# CAMERA_DVP_FPC24_OV2640_8bit.net
KiCad netlist of a schematic drawn in Altium Designer
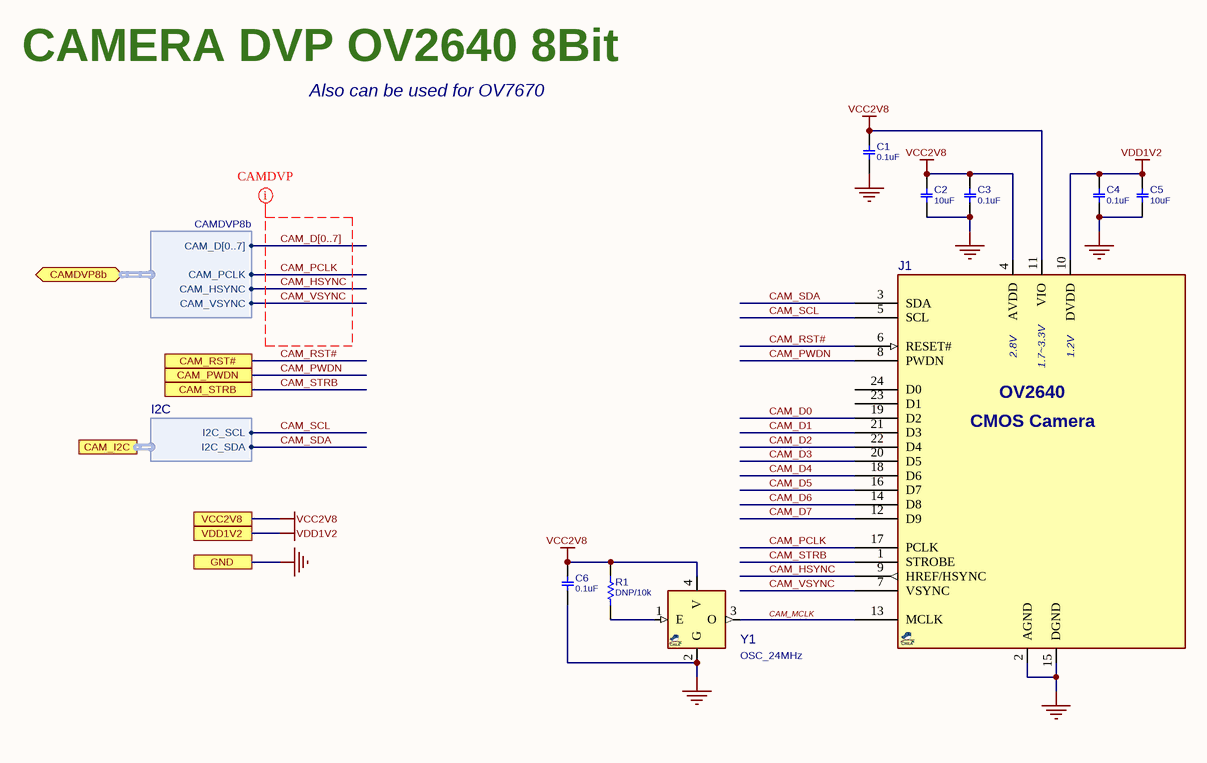
[diagram p0: CAMERA_DVP_FPC24_OV2640_8bit.SchDoc]

(export (version "E")
  (design (tool "Eeschema 10.0.6"))
  (components
    (comp (ref "C1")
      (value "0.1uF")
      (footprint "C0402")
      (description "CAP, MLCC")
      (libsource (lib "mlcc_smd_passive") (part "CAP_SMD_MLCC_100n50TDK"))
    )
    (comp (ref "C2")
      (value "10uF")
      (footprint "C0402")
      (description "CAP, MLCC")
      (libsource (lib "mlcc_smd_passive") (part "CAP_SMD_MLCC_100n50TDK"))
    )
    (comp (ref "C3")
      (value "0.1uF")
      (footprint "C0402")
      (description "CAP, MLCC")
      (libsource (lib "mlcc_smd_passive") (part "CAP_SMD_MLCC_100n50TDK"))
    )
    (comp (ref "C4")
      (value "0.1uF")
      (footprint "C0402")
      (description "CAP, MLCC")
      (libsource (lib "mlcc_smd_passive") (part "CAP_SMD_MLCC_100n50TDK"))
    )
    (comp (ref "C5")
      (value "10uF")
      (footprint "C0402")
      (description "CAP, MLCC")
      (libsource (lib "mlcc_smd_passive") (part "CAP_SMD_MLCC_100n50TDK"))
    )
    (comp (ref "C6")
      (value "0.1uF")
      (footprint "C0402")
      (description "CAP, MLCC")
      (libsource (lib "mlcc_smd_passive") (part "CAP_SMD_MLCC_100n50TDK"))
    )
    (comp (ref "J1")
      (value "OV2640")
      (footprint "FPC50_24")
      (description "Camera Module, Color CMOS 2MP, DVP FPC24")
      (libsource (lib "camera") (part "OV2640_FPC24"))
    )
    (comp (ref "R1")
      (value "DNP/10k")
      (footprint "R0402")
      (description "RESISTOR, SMD, THICK FILM, YAGEO")
      (fields (field (name "MANF_P#") "RC0402FR-071KL") (field (name "MANF") "Yageo"))
      (libsource (lib "res_smd_Yageo0402_thickfilm") (part "RES_SMD_1K_0402YK"))
    )
    (comp (ref "Y1")
      (value "OSC_24MHz")
      (footprint "XTL_4_2016")
      (description "CLOCK OSCILLATOR")
      (fields (field (name "MANF") "ECS"))
      (libsource (lib "crystal_osc") (part "OSC_4_25MHz_3225E"))
    )
  )
  (nets
    (net (code "3") (name "/CAM_D0") (class "Default")
      (node (ref "J1") (pin "19") (pinfunction "D2_19") (pintype "passive"))
    )
    (net (code "4") (name "/CAM_D1") (class "Default")
      (node (ref "J1") (pin "21") (pinfunction "D3_21") (pintype "passive"))
    )
    (net (code "5") (name "/CAM_D2") (class "Default")
      (node (ref "J1") (pin "22") (pinfunction "D4_22") (pintype "passive"))
    )
    (net (code "6") (name "/CAM_D3") (class "Default")
      (node (ref "J1") (pin "20") (pinfunction "D5_20") (pintype "passive"))
    )
    (net (code "7") (name "/CAM_D4") (class "Default")
      (node (ref "J1") (pin "18") (pinfunction "D6_18") (pintype "passive"))
    )
    (net (code "8") (name "/CAM_D5") (class "Default")
      (node (ref "J1") (pin "16") (pinfunction "D7_16") (pintype "passive"))
    )
    (net (code "9") (name "/CAM_D6") (class "Default")
      (node (ref "J1") (pin "14") (pinfunction "D8_14") (pintype "passive"))
    )
    (net (code "10") (name "/CAM_D7") (class "Default")
      (node (ref "J1") (pin "12") (pinfunction "D9_12") (pintype "passive"))
    )
    (net (code "12") (name "/CAM_HSYNC") (class "Default")
      (node (ref "J1") (pin "9") (pinfunction "HREF/HSYNC_9") (pintype "output"))
    )
    (net (code "13") (name "/CAM_MCLK") (class "Default")
      (node (ref "J1") (pin "13") (pinfunction "MCLK_13") (pintype "passive"))
      (node (ref "Y1") (pin "3") (pinfunction "O_3") (pintype "output"))
    )
    (net (code "14") (name "/CAM_PCLK") (class "Default")
      (node (ref "J1") (pin "17") (pinfunction "PCLK_17") (pintype "passive"))
    )
    (net (code "15") (name "/CAM_PWDN") (class "Default")
      (node (ref "J1") (pin "8") (pinfunction "PWDN_8") (pintype "passive"))
    )
    (net (code "16") (name "/CAM_RST#") (class "Default")
      (node (ref "J1") (pin "6") (pinfunction "RESET#_6") (pintype "input"))
    )
    (net (code "17") (name "/CAM_SCL") (class "Default")
      (node (ref "J1") (pin "5") (pinfunction "SCL_5") (pintype "passive"))
    )
    (net (code "18") (name "/CAM_SDA") (class "Default")
      (node (ref "J1") (pin "3") (pinfunction "SDA_3") (pintype "passive"))
    )
    (net (code "19") (name "/CAM_STRB") (class "Default")
      (node (ref "J1") (pin "1") (pinfunction "STROBE_1") (pintype "passive"))
    )
    (net (code "20") (name "/CAM_VSYNC") (class "Default")
      (node (ref "J1") (pin "7") (pinfunction "VSYNC_7") (pintype "passive"))
    )
    (net (code "23") (name "GND") (class "Default")
      (node (ref "C1") (pin "2") (pinfunction "2_2") (pintype "passive"))
      (node (ref "C2") (pin "2") (pinfunction "2_2") (pintype "passive"))
      (node (ref "C3") (pin "2") (pinfunction "2_2") (pintype "passive"))
      (node (ref "C4") (pin "2") (pinfunction "2_2") (pintype "passive"))
      (node (ref "C5") (pin "2") (pinfunction "2_2") (pintype "passive"))
      (node (ref "C6") (pin "2") (pinfunction "2_2") (pintype "passive"))
      (node (ref "J1") (pin "15") (pinfunction "DGND_15") (pintype "power_in"))
      (node (ref "J1") (pin "2") (pinfunction "AGND_2") (pintype "power_in"))
      (node (ref "Y1") (pin "2") (pinfunction "G_2") (pintype "power_in"))
    )
    (net (code "24") (name "Net-(Y1-E)") (class "Default")
      (node (ref "R1") (pin "2") (pinfunction "2_2") (pintype "passive"))
      (node (ref "Y1") (pin "1") (pinfunction "E_1") (pintype "input"))
    )
    (net (code "25") (name "VCC2V8") (class "Default")
      (node (ref "C1") (pin "1") (pinfunction "1_1") (pintype "passive"))
      (node (ref "C2") (pin "1") (pinfunction "1_1") (pintype "passive"))
      (node (ref "C3") (pin "1") (pinfunction "1_1") (pintype "passive"))
      (node (ref "C6") (pin "1") (pinfunction "1_1") (pintype "passive"))
      (node (ref "J1") (pin "11") (pinfunction "VIO_11") (pintype "power_in"))
      (node (ref "J1") (pin "4") (pinfunction "AVDD_4") (pintype "power_in"))
      (node (ref "R1") (pin "1") (pinfunction "1_1") (pintype "passive"))
      (node (ref "Y1") (pin "4") (pinfunction "V_4") (pintype "power_in"))
    )
    (net (code "26") (name "VDD1V2") (class "Default")
      (node (ref "C4") (pin "1") (pinfunction "1_1") (pintype "passive"))
      (node (ref "C5") (pin "1") (pinfunction "1_1") (pintype "passive"))
      (node (ref "J1") (pin "10") (pinfunction "DVDD_10") (pintype "power_in"))
    )
    (net (code "27") (name "unconnected-(J1-D0-Pad24)") (class "Default")
      (node (ref "J1") (pin "24") (pinfunction "D0_24") (pintype "passive"))
    )
    (net (code "28") (name "unconnected-(J1-D1-Pad23)") (class "Default")
      (node (ref "J1") (pin "23") (pinfunction "D1_23") (pintype "passive"))
    )
  )
)
